# Bandgap_Reference.net
KiCad netlist of a schematic drawn in Altium Designer
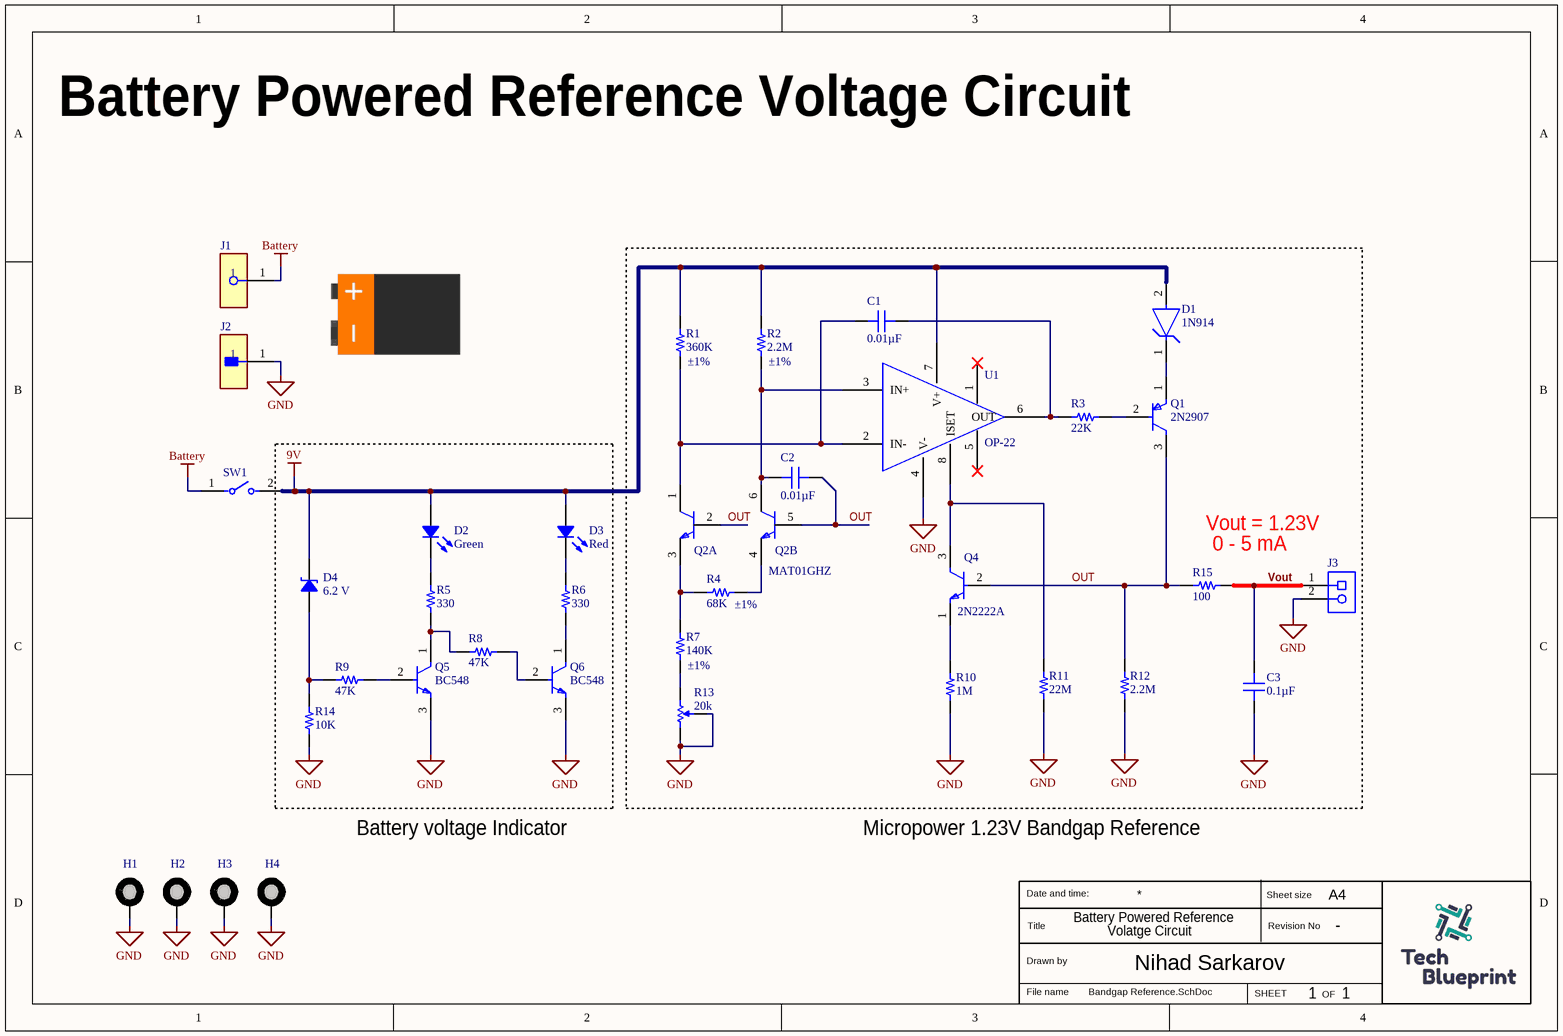
[diagram p0: Bandgap Reference.SchDoc]

(export (version "E")
  (design (tool "Eeschema 10.0.6"))
  (components
    (comp (ref "C1")
      (value "10000 pF")
      (footprint "CAP 1206_3216 - 0.8MM")
      (description "CAP CER 1206 10NF 250V X7R 10%")
      (fields
        (field (name "PART NUMBER") "C1206C103KARECAUTO")
        (field (name "CAPACITANCE") "0.01µF")
        (field (name "MANUFACTURER") "KEMET")
      )
      (libsource (lib "Celestial Altium Library - altium_library") (part "Capacitor"))
    )
    (comp (ref "C2")
      (value "10000 pF")
      (footprint "CAP 1206_3216 - 0.8MM")
      (description "CAP CER 1206 10NF 250V X7R 10%")
      (fields
        (field (name "PART NUMBER") "C1206C103KARECAUTO")
        (field (name "CAPACITANCE") "0.01µF")
        (field (name "MANUFACTURER") "KEMET")
      )
      (libsource (lib "Celestial Altium Library - altium_library") (part "Capacitor"))
    )
    (comp (ref "C3")
      (value "0.1µF")
      (footprint "CAP 1206_3216 - 1.0MM")
      (description "CAP CER 0.1UF 50V X7R 1206")
      (fields
        (field (name "PART NUMBER") "LD065C104KAB2A")
        (field (name "CAPACITANCE") "0.1µF")
        (field (name "MANUFACTURER") "AVX Corporation")
      )
      (libsource (lib "Celestial Altium Library - altium_library") (part "Capacitor"))
    )
    (comp (ref "D1")
      (value "1N914")
      (footprint "FP-DO-213AA-MFG")
      (description "JANTX1N914UR Signal Or Computer Diode Do-213Aa Rohs Compliant: Yes")
      (libsource (lib "Altium Content Vault") (part "f813f71cba58e380607f5dd3caf9714"))
    )
    (comp (ref "D2")
      (value "Green")
      (footprint "LED 1206_3216 GREEN")
      (description "LED GREEN CLEAR CHIP SMD")
      (fields (field (name "PART NUMBER") "APT3216SGC") (field (name "MANUFACTURER") "Kingbright"))
      (libsource (lib "Celestial Altium Library - altium_library") (part "LED"))
    )
    (comp (ref "D3")
      (value "Red")
      (footprint "LED 1206_3216 RED")
      (description "LED RED CHIP SMD")
      (fields (field (name "PART NUMBER") "HSMC-C350") (field (name "MANUFACTURER") "Broadcom Limited"))
      (libsource (lib "Celestial Altium Library - altium_library") (part "LED"))
    )
    (comp (ref "D4")
      (value "BZX84W-B6V2F")
      (footprint "DIODES SOT-323-3")
      (description "DIODE ZENER 6.2V 275MW SOT323")
      (fields
        (field (name "MANUFACTURER") "Nexperia USA Inc.")
        (field (name "TOLERANCE") "±2%")
        (field (name "VOLTAGE - ZENER (NOM) (VZ)") "6.2 V")
      )
      (libsource (lib "Celestial Altium Library - altium_library") (part "Diode Zener"))
    )
    (comp (ref "H1")
      (value "Mounting Hole")
      (footprint "Mounting Hole")
      (libsource (lib "TC427IJA") (part "Mounting Hole"))
    )
    (comp (ref "H2")
      (value "Mounting Hole")
      (footprint "Mounting Hole")
      (libsource (lib "TC427IJA") (part "Mounting Hole"))
    )
    (comp (ref "H3")
      (value "Mounting Hole")
      (footprint "Mounting Hole")
      (libsource (lib "TC427IJA") (part "Mounting Hole"))
    )
    (comp (ref "H4")
      (value "Mounting Hole")
      (footprint "Mounting Hole")
      (libsource (lib "TC427IJA") (part "Mounting Hole"))
    )
    (comp (ref "J1")
      (value "594")
      (footprint "FP-594-MFG")
      (description "BATTERY CONTACT SNAP 9V PC PIN")
      (libsource (lib "Altium Content Vault") (part "c5c826e0c4b67fe3b42ef77f2d4decc"))
    )
    (comp (ref "J2")
      (value "593")
      (footprint "FP-593-MFG")
      (description "BATTERY CONTACT SNAP 9V PC PIN")
      (libsource (lib "Altium Content Vault") (part "dd45045ce8184df9e99e12baf3f412c"))
    )
    (comp (ref "J3")
      (value "1729128")
      (footprint "PHOE-1729128-2_V")
      (description "PCB Terminal Block, 13.5 A, 400 V, 2-Pin THD, RoHS, Bulk")
      (fields (field (name "MANUFACTURER") "Phoenix Contact"))
      (libsource (lib "Altium Content Vault") (part "CN-2P-F-R2"))
    )
    (comp (ref "Q1")
      (value "2N2907")
      (footprint "FP-TO-18-MFG")
      (description "2N2907 Small-Signal Bjt To-18 Rohs Compliant: Yes")
      (libsource (lib "Altium Content Vault") (part "15b317111ce8998a8cd3923a58ba97d"))
    )
    (comp (ref "Q2")
      (value "MAT01GHZ")
      (footprint "FP-H-06-MFG")
      (description "TRANS 2NPN 45V 0.025A TO78-6")
      (libsource (lib "TC427IJA") (part "MAT01GHZ"))
    )
    (comp (ref "Q4")
      (value "2N2222A")
      (footprint "FP-2N2222A-MFG")
      (description "T-NPN SI- AUDIO VHF AMP")
      (libsource (lib "Altium Content Vault") (part "a64cbfbad643015290886283bc510aa"))
    )
    (comp (ref "Q5")
      (value "BC548")
      (footprint "FP-135AN-MFG")
      (description "BC548 Bulk Through Hole NPN Single Bipolar (BJT) Transistor 110 @ 2mA 5V 100mA 500mW 300MHz")
      (libsource (lib "Altium Content Vault") (part "0e34aa19c3f436cc9ae3cb3686437ec"))
    )
    (comp (ref "Q6")
      (value "BC548")
      (footprint "FP-135AN-MFG")
      (description "BC548 Bulk Through Hole NPN Single Bipolar (BJT) Transistor 110 @ 2mA 5V 100mA 500mW 300MHz")
      (libsource (lib "Altium Content Vault") (part "0e34aa19c3f436cc9ae3cb3686437ec"))
    )
    (comp (ref "R1")
      (value "360K")
      (footprint "RES 1206_3216")
      (description "3430 B2 1% 360K 100PPM 1K RL")
      (fields
        (field (name "PART NUMBER") "3430B2F360KTDF")
        (field (name "MANUFACTURER") "TE Connectivity Passive Product")
        (field (name "TOLERANCE") "±1%")
      )
      (libsource (lib "Celestial Altium Library - altium_library") (part "Resistor"))
    )
    (comp (ref "R2")
      (value "2.2M")
      (footprint "RES 1206_3216")
      (description "RES 2.2M OHM 1% 0.66W 1206")
      (fields
        (field (name "PART NUMBER") "ERJ-PM8F2204V")
        (field (name "MANUFACTURER") "Panasonic Electronic Components")
        (field (name "TOLERANCE") "±1%")
      )
      (libsource (lib "Celestial Altium Library - altium_library") (part "Resistor"))
    )
    (comp (ref "R3")
      (value "22K")
      (footprint "RES 1206_3216")
      (description "3430 B2 1% 22K 100PPM 1K RL")
      (fields
        (field (name "PART NUMBER") "3430B2F22KTDF")
        (field (name "MANUFACTURER") "TE Connectivity Passive Product")
      )
      (libsource (lib "Celestial Altium Library - altium_library") (part "Resistor"))
    )
    (comp (ref "R4")
      (value "68K")
      (footprint "RES 1206_3216")
      (description "3430 B2 1% 68K 100PPM 1K RL")
      (fields
        (field (name "PART NUMBER") "3430B2F68KTDF")
        (field (name "MANUFACTURER") "TE Connectivity Passive Product")
        (field (name "TOLERANCE") "±1%")
      )
      (libsource (lib "Celestial Altium Library - altium_library") (part "Resistor"))
    )
    (comp (ref "R5")
      (value "330")
      (footprint "RES 1206_3216")
      (description "RCS1206 200 330R 5% ET1 E3")
      (fields (field (name "PART NUMBER") "RCS1206330RJNEA") (field (name "MANUFACTURER") "Vishay Dale"))
      (libsource (lib "Celestial Altium Library - altium_library") (part "Resistor"))
    )
    (comp (ref "R6")
      (value "330")
      (footprint "RES 1206_3216")
      (description "RCS1206 200 330R 5% ET1 E3")
      (fields (field (name "PART NUMBER") "RCS1206330RJNEA") (field (name "MANUFACTURER") "Vishay Dale"))
      (libsource (lib "Celestial Altium Library - altium_library") (part "Resistor"))
    )
    (comp (ref "R7")
      (value "140K")
      (footprint "RES 1206_3216")
      (description "RES 140K OHM 1% 1/4W 1206")
      (fields
        (field (name "PART NUMBER") "RMCF1206FT140K")
        (field (name "MANUFACTURER") "Stackpole Electronics Inc")
        (field (name "TOLERANCE") "±1%")
      )
      (libsource (lib "Celestial Altium Library - altium_library") (part "Resistor"))
    )
    (comp (ref "R8")
      (value "47K")
      (footprint "RES 1206_3216")
      (description "RES SMD 47K OHM 3/4W 1206 WIDE")
      (fields (field (name "PART NUMBER") "RCL061247K0JNEA") (field (name "MANUFACTURER") "Vishay Dale"))
      (libsource (lib "Celestial Altium Library - altium_library") (part "Resistor"))
    )
    (comp (ref "R9")
      (value "47K")
      (footprint "RES 1206_3216")
      (description "RES SMD 47K OHM 3/4W 1206 WIDE")
      (fields (field (name "PART NUMBER") "RCL061247K0JNEA") (field (name "MANUFACTURER") "Vishay Dale"))
      (libsource (lib "Celestial Altium Library - altium_library") (part "Resistor"))
    )
    (comp (ref "R10")
      (value "1M")
      (footprint "RES 1206_3216")
      (description "3430 B2 1% 1M0 100PPM 1K RL")
      (fields
        (field (name "PART NUMBER") "3430B2F1M0TDF")
        (field (name "MANUFACTURER") "TE Connectivity Passive Product")
      )
      (libsource (lib "Celestial Altium Library - altium_library") (part "Resistor"))
    )
    (comp (ref "R11")
      (value "22M")
      (footprint "RES 1206_3216")
      (description "RES SMD 22M OHM 1% 1/4W 1206")
      (fields
        (field (name "PART NUMBER") "CRG1206F22M")
        (field (name "MANUFACTURER") "TE Connectivity Passive Product")
      )
      (libsource (lib "Celestial Altium Library - altium_library") (part "Resistor"))
    )
    (comp (ref "R12")
      (value "2.2M")
      (footprint "RES 1206_3216")
      (description "RES 2.2M OHM 1% 0.66W 1206")
      (fields
        (field (name "PART NUMBER") "ERJ-PM8F2204V")
        (field (name "MANUFACTURER") "Panasonic Electronic Components")
      )
      (libsource (lib "Celestial Altium Library - altium_library") (part "Resistor"))
    )
    (comp (ref "R13")
      (value "3313J-1-203E")
      (footprint "BOUR-3313J-1_V")
      (fields
        (field (name "MANUFACTURER") "Bourns")
        (field (name "RESISTANCE") "20k")
        (field (name "TOLERANCE") "±20%")
      )
      (libsource (lib "Altium Content Vault") (part "RES-ADJ-3_A"))
    )
    (comp (ref "R14")
      (value "10K")
      (footprint "RES 1206_3216")
      (description "RCC1206 200 10K 5% ET1 E3")
      (fields (field (name "PART NUMBER") "RCC120610K0JNEA") (field (name "MANUFACTURER") "Vishay Dale"))
      (libsource (lib "Celestial Altium Library - altium_library") (part "Resistor"))
    )
    (comp (ref "R15")
      (value "100")
      (footprint "RES 1206_3216")
      (description "3430 B2 1% 100R 100PPM 1K RL")
      (fields
        (field (name "PART NUMBER") "3430B2F100RTDF")
        (field (name "MANUFACTURER") "TE Connectivity Passive Product")
      )
      (libsource (lib "Celestial Altium Library - altium_library") (part "Resistor"))
    )
    (comp (ref "SW1")
      (value "BD01")
      (footprint "FP-BD01-MFG")
      (description "SWITCH SLIDE DIP SPST 100MA 5V")
      (libsource (lib "Altium Content Vault") (part "bb27bde45df87f1f469753f287ef5ae"))
    )
    (comp (ref "U1")
      (value "OP-22")
      (footprint "CERDIP8_300MC_MCH")
      (description "Programmable micropower operational amplifier")
      (libsource (lib "TC427IJA") (part "OP-22"))
    )
  )
  (nets
    (net (code "1") (name "/OUT") (class "Default")
      (node (ref "C2") (pin "2") (pinfunction "2_2") (pintype "passive"))
      (node (ref "Q1") (pin "3") (pinfunction "C_3") (pintype "passive"))
      (node (ref "Q2") (pin "2") (pinfunction "2_2") (pintype "passive"))
      (node (ref "Q2") (pin "5") (pinfunction "5_5") (pintype "passive"))
      (node (ref "Q4") (pin "2") (pinfunction "B_2") (pintype "passive"))
      (node (ref "R12") (pin "2") (pinfunction "2_2") (pintype "passive"))
      (node (ref "R15") (pin "1") (pinfunction "1_1") (pintype "passive"))
    )
    (net (code "2") (name "/Vout") (class "Default")
      (node (ref "C3") (pin "2") (pinfunction "2_2") (pintype "passive"))
      (node (ref "J3") (pin "1") (pinfunction "1_1") (pintype "passive"))
      (node (ref "R15") (pin "2") (pinfunction "2_2") (pintype "passive"))
    )
    (net (code "3") (name "9V") (class "Default")
      (node (ref "D1") (pin "2") (pinfunction "A_2") (pintype "passive"))
      (node (ref "D2") (pin "1") (pinfunction "1_1") (pintype "passive"))
      (node (ref "D3") (pin "1") (pinfunction "1_1") (pintype "passive"))
      (node (ref "D4") (pin "2") (pinfunction "2_2") (pintype "passive"))
      (node (ref "R1") (pin "2") (pinfunction "2_2") (pintype "passive"))
      (node (ref "R2") (pin "2") (pinfunction "2_2") (pintype "passive"))
      (node (ref "SW1") (pin "2") (pinfunction "2_2") (pintype "passive"))
      (node (ref "U1") (pin "7") (pinfunction "V+_7") (pintype "passive"))
    )
    (net (code "4") (name "Battery") (class "Default")
      (node (ref "J1") (pin "1") (pinfunction "1_1") (pintype "passive"))
      (node (ref "SW1") (pin "1") (pinfunction "1_1") (pintype "passive"))
    )
    (net (code "5") (name "GND") (class "Default")
      (node (ref "C3") (pin "1") (pinfunction "1_1") (pintype "passive"))
      (node (ref "H1") (pin "1") (pinfunction "1_1") (pintype "passive"))
      (node (ref "H2") (pin "1") (pinfunction "1_1") (pintype "passive"))
      (node (ref "H3") (pin "1") (pinfunction "1_1") (pintype "passive"))
      (node (ref "H4") (pin "1") (pinfunction "1_1") (pintype "passive"))
      (node (ref "J2") (pin "1") (pinfunction "1_1") (pintype "passive"))
      (node (ref "J3") (pin "2") (pinfunction "2_2") (pintype "passive"))
      (node (ref "Q5") (pin "3") (pinfunction "E_3") (pintype "passive"))
      (node (ref "Q6") (pin "3") (pinfunction "E_3") (pintype "passive"))
      (node (ref "R10") (pin "1") (pinfunction "1_1") (pintype "passive"))
      (node (ref "R11") (pin "1") (pinfunction "1_1") (pintype "passive"))
      (node (ref "R12") (pin "1") (pinfunction "1_1") (pintype "passive"))
      (node (ref "R13") (pin "1") (pinfunction "1_1") (pintype "passive"))
      (node (ref "R13") (pin "2") (pinfunction "2_2") (pintype "passive"))
      (node (ref "R14") (pin "1") (pinfunction "1_1") (pintype "passive"))
      (node (ref "U1") (pin "4") (pinfunction "V-_4") (pintype "passive"))
    )
    (net (code "6") (name "Net-(D1-C)") (class "Default")
      (node (ref "D1") (pin "1") (pinfunction "C_1") (pintype "passive"))
      (node (ref "Q1") (pin "1") (pinfunction "E_1") (pintype "passive"))
    )
    (net (code "7") (name "Net-(D2-Pad2)") (class "Default")
      (node (ref "D2") (pin "2") (pinfunction "2_2") (pintype "passive"))
      (node (ref "R5") (pin "2") (pinfunction "2_2") (pintype "passive"))
    )
    (net (code "8") (name "Net-(D3-Pad2)") (class "Default")
      (node (ref "D3") (pin "2") (pinfunction "2_2") (pintype "passive"))
      (node (ref "R6") (pin "2") (pinfunction "2_2") (pintype "passive"))
    )
    (net (code "9") (name "Net-(D4-Pad1)") (class "Default")
      (node (ref "D4") (pin "1") (pinfunction "1_1") (pintype "passive"))
      (node (ref "R14") (pin "2") (pinfunction "2_2") (pintype "passive"))
      (node (ref "R9") (pin "1") (pinfunction "1_1") (pintype "passive"))
    )
    (net (code "10") (name "Net-(Q1-B)") (class "Default")
      (node (ref "Q1") (pin "2") (pinfunction "B_2") (pintype "passive"))
      (node (ref "R3") (pin "2") (pinfunction "2_2") (pintype "passive"))
    )
    (net (code "11") (name "Net-(Q2-Pad3)") (class "Default")
      (node (ref "Q2") (pin "3") (pinfunction "3_3") (pintype "passive"))
      (node (ref "R4") (pin "1") (pinfunction "1_1") (pintype "passive"))
      (node (ref "R7") (pin "2") (pinfunction "2_2") (pintype "passive"))
    )
    (net (code "12") (name "Net-(Q2-Pad4)") (class "Default")
      (node (ref "Q2") (pin "4") (pinfunction "4_4") (pintype "passive"))
      (node (ref "R4") (pin "2") (pinfunction "2_2") (pintype "passive"))
    )
    (net (code "13") (name "Net-(Q4-C)") (class "Default")
      (node (ref "Q4") (pin "3") (pinfunction "C_3") (pintype "passive"))
      (node (ref "R11") (pin "2") (pinfunction "2_2") (pintype "passive"))
      (node (ref "U1") (pin "8") (pinfunction "ISET_8") (pintype "passive"))
    )
    (net (code "14") (name "Net-(Q4-E)") (class "Default")
      (node (ref "Q4") (pin "1") (pinfunction "E_1") (pintype "passive"))
      (node (ref "R10") (pin "2") (pinfunction "2_2") (pintype "passive"))
    )
    (net (code "15") (name "Net-(Q5-B)") (class "Default")
      (node (ref "Q5") (pin "2") (pinfunction "B_2") (pintype "passive"))
      (node (ref "R9") (pin "2") (pinfunction "2_2") (pintype "passive"))
    )
    (net (code "16") (name "Net-(Q5-C)") (class "Default")
      (node (ref "Q5") (pin "1") (pinfunction "C_1") (pintype "passive"))
      (node (ref "R5") (pin "1") (pinfunction "1_1") (pintype "passive"))
      (node (ref "R8") (pin "1") (pinfunction "1_1") (pintype "passive"))
    )
    (net (code "17") (name "Net-(Q6-B)") (class "Default")
      (node (ref "Q6") (pin "2") (pinfunction "B_2") (pintype "passive"))
      (node (ref "R8") (pin "2") (pinfunction "2_2") (pintype "passive"))
    )
    (net (code "18") (name "Net-(Q6-C)") (class "Default")
      (node (ref "Q6") (pin "1") (pinfunction "C_1") (pintype "passive"))
      (node (ref "R6") (pin "1") (pinfunction "1_1") (pintype "passive"))
    )
    (net (code "19") (name "Net-(R13-Pad3)") (class "Default")
      (node (ref "R13") (pin "3") (pinfunction "3_3") (pintype "passive"))
      (node (ref "R7") (pin "1") (pinfunction "1_1") (pintype "passive"))
    )
    (net (code "20") (name "Net-(U1-IN+)") (class "Default")
      (node (ref "C2") (pin "1") (pinfunction "1_1") (pintype "passive"))
      (node (ref "Q2") (pin "6") (pinfunction "6_6") (pintype "passive"))
      (node (ref "R2") (pin "1") (pinfunction "1_1") (pintype "passive"))
      (node (ref "U1") (pin "3") (pinfunction "IN+_3") (pintype "passive"))
    )
    (net (code "21") (name "Net-(U1-IN-)") (class "Default")
      (node (ref "C1") (pin "1") (pinfunction "1_1") (pintype "passive"))
      (node (ref "Q2") (pin "1") (pinfunction "1_1") (pintype "passive"))
      (node (ref "R1") (pin "1") (pinfunction "1_1") (pintype "passive"))
      (node (ref "U1") (pin "2") (pinfunction "IN-_2") (pintype "passive"))
    )
    (net (code "22") (name "Net-(U1-OUT)") (class "Default")
      (node (ref "C1") (pin "2") (pinfunction "2_2") (pintype "passive"))
      (node (ref "R3") (pin "1") (pinfunction "1_1") (pintype "passive"))
      (node (ref "U1") (pin "6") (pinfunction "OUT_6") (pintype "passive"))
    )
    (net (code "23") (name "unconnected-(U1-BAL-Pad1)") (class "Default")
      (node (ref "U1") (pin "1") (pinfunction "BAL_1") (pintype "passive+no_connect"))
    )
    (net (code "24") (name "unconnected-(U1-BAL-Pad5)") (class "Default")
      (node (ref "U1") (pin "5") (pinfunction "BAL_5") (pintype "passive+no_connect"))
    )
  )
)
